# 111.net
KiCad netlist of a schematic drawn in Altium Designer
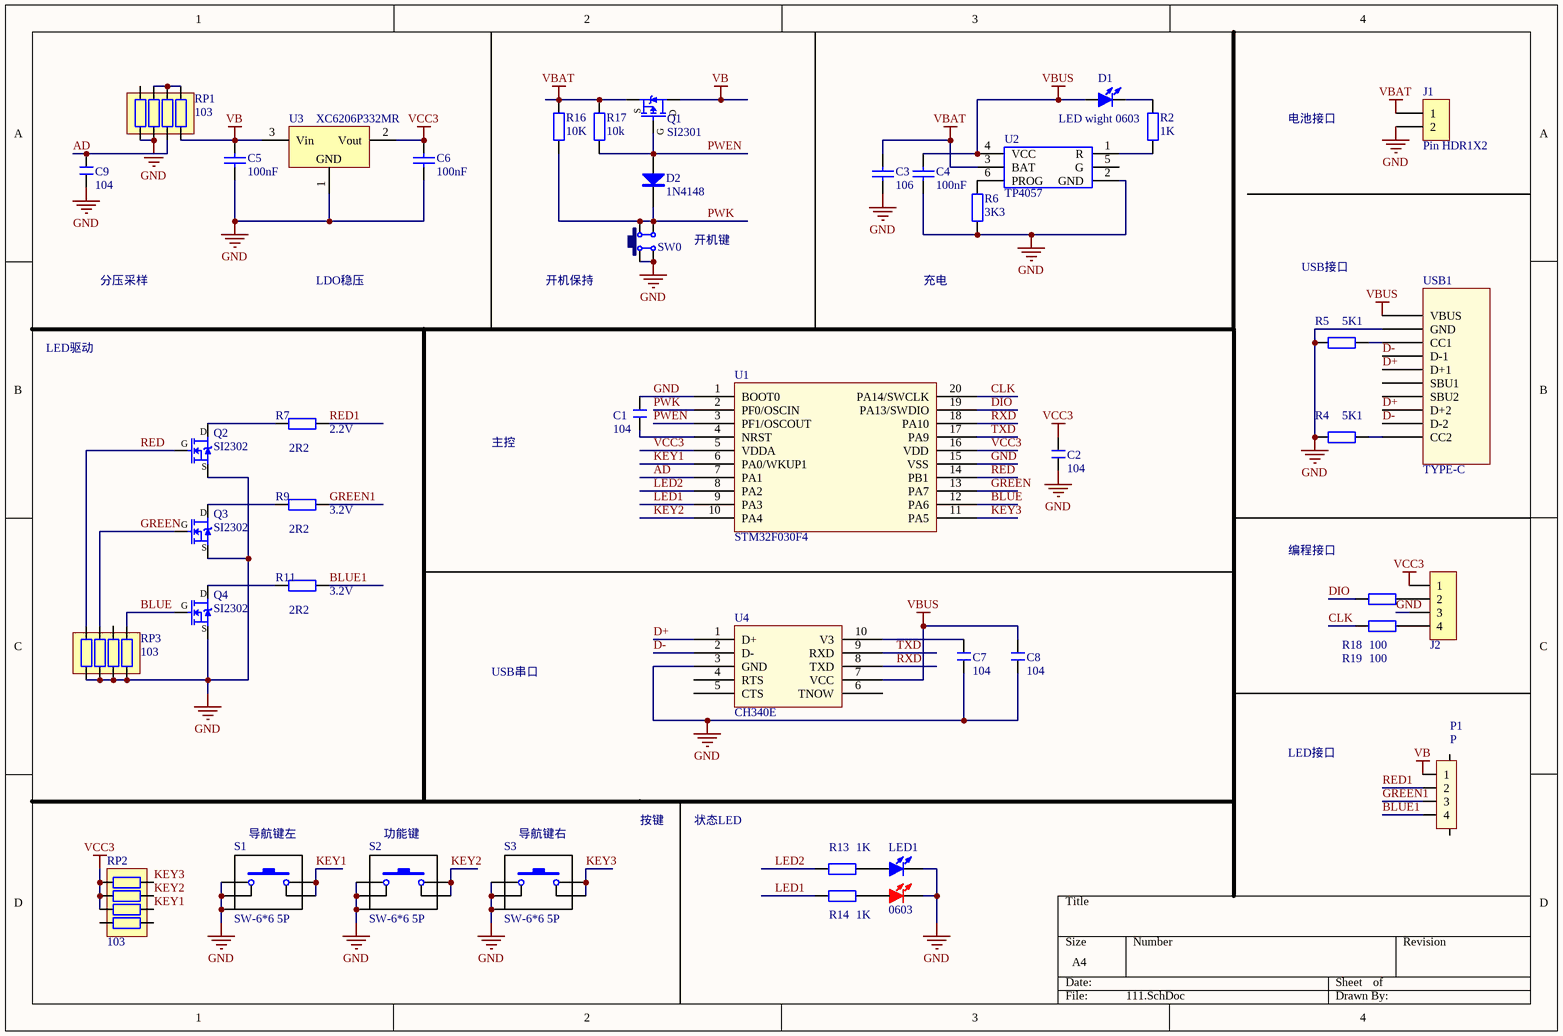
[diagram p0: 111.SchDoc]

(export (version "E")
  (design (tool "Eeschema 10.0.6"))
  (components
    (comp (ref "C1")
      (value "104")
      (footprint "C 0402_M")
      (description "无极性贴片电容")
      (libsource (lib "3.1   - 电阻-电容-电感") (part "C"))
    )
    (comp (ref "C2")
      (value "104")
      (footprint "C 0402_M")
      (description "无极性贴片电容")
      (libsource (lib "3.1   - 电阻-电容-电感") (part "C"))
    )
    (comp (ref "C3")
      (value "106")
      (footprint "C-RAD-0805")
      (description "无极性电容")
      (fields (field (name "Comment") "Cap") (field (name "PUBLISHER") "Altium Limited"))
      (libsource (lib "fszhang") (part "Cap"))
    )
    (comp (ref "C4")
      (value "100nF")
      (footprint "C-RAD-0603")
      (description "无极性电容")
      (fields (field (name "Comment") "Cap") (field (name "PUBLISHER") "Altium Limited"))
      (libsource (lib "fszhang") (part "Cap"))
    )
    (comp (ref "C5")
      (value "100nF")
      (footprint "C-RAD-0603")
      (description "无极性电容")
      (fields (field (name "Comment") "Cap") (field (name "PUBLISHER") "Altium Limited"))
      (libsource (lib "fszhang") (part "Cap"))
    )
    (comp (ref "C6")
      (value "100nF")
      (footprint "C-RAD-0603")
      (description "无极性电容")
      (fields (field (name "Comment") "Cap") (field (name "PUBLISHER") "Altium Limited"))
      (libsource (lib "fszhang") (part "Cap"))
    )
    (comp (ref "C7")
      (value "104")
      (footprint "C 0402_M")
      (description "无极性贴片电容")
      (libsource (lib "3.1   - 电阻-电容-电感") (part "C"))
    )
    (comp (ref "C8")
      (value "104")
      (footprint "C 0402_M")
      (description "无极性贴片电容")
      (libsource (lib "3.1   - 电阻-电容-电感") (part "C"))
    )
    (comp (ref "C9")
      (value "104")
      (footprint "C 0402_M")
      (description "无极性贴片电容")
      (libsource (lib "3.1   - 电阻-电容-电感") (part "C"))
    )
    (comp (ref "D1")
      (value "LED wight 0603")
      (footprint "LED 0603R")
      (description "贴片LED")
      (libsource (lib "9.1   - LED") (part "LED-SMD"))
    )
    (comp (ref "D2")
      (value "1N4148")
      (footprint "SOD-323")
      (description "高速开关二极管")
      (libsource (lib "8.1   - 二极管-整流桥") (part "1N4148"))
    )
    (comp (ref "J1") (value "Pin HDR1X2") (footprint "SH1.0_2pin") (libsource (lib "排针") (part "Pin HDR1X2")))
    (comp (ref "J2")
      (value "HDR-1X4")
      (footprint "HDR2.0-LI-4P")
      (description "4P接插件")
      (libsource (lib "4.5   - 接插件-脚距2.0") (part "Header 4"))
    )
    (comp (ref "LED1")
      (value "0603")
      (footprint "LED 0603-RG")
      (description "贴片双色LED")
      (libsource (lib "9.1   - LED") (part "LED-SMD-RG"))
    )
    (comp (ref "P1") (value "P") (footprint "SH1.0_4pin") (libsource (lib "0") (part "SH1.0-4")))
    (comp (ref "Q1")
      (value "SI2301")
      (footprint "SOT23-3N")
      (description "P沟道 20V/2.8A")
      (libsource (lib "6.1   - 场效应管-可控硅") (part "SI2301"))
    )
    (comp (ref "Q2")
      (value "SI2302")
      (footprint "SOT23-3N")
      (description "N沟道 20V/3A")
      (libsource (lib "6.1   - 场效应管-可控硅") (part "SI2302"))
    )
    (comp (ref "Q3")
      (value "SI2302")
      (footprint "SOT23-3N")
      (description "N沟道 20V/3A")
      (libsource (lib "6.1   - 场效应管-可控硅") (part "SI2302"))
    )
    (comp (ref "Q4")
      (value "SI2302")
      (footprint "SOT23-3N")
      (description "N沟道 20V/3A")
      (libsource (lib "6.1   - 场效应管-可控硅") (part "SI2302"))
    )
    (comp (ref "R2")
      (value "1K")
      (footprint "R 0402_M")
      (description "贴片电阻")
      (libsource (lib "3.1   - 电阻-电容-电感") (part "R"))
    )
    (comp (ref "R4")
      (value "5K1")
      (footprint "R 0402_M")
      (description "贴片电阻")
      (libsource (lib "3.1   - 电阻-电容-电感") (part "R"))
    )
    (comp (ref "R5")
      (value "5K1")
      (footprint "R 0402_M")
      (description "贴片电阻")
      (libsource (lib "3.1   - 电阻-电容-电感") (part "R"))
    )
    (comp (ref "R6")
      (value "3K3")
      (footprint "R 0402_M")
      (description "贴片电阻")
      (libsource (lib "3.1   - 电阻-电容-电感") (part "R"))
    )
    (comp (ref "R7")
      (value "2R2")
      (footprint "0603-1")
      (description "贴片电阻")
      (fields (field (name "PUBLISHER") "Altium Limited"))
      (libsource (lib "fszhang") (part "Res1"))
    )
    (comp (ref "R9")
      (value "2R2")
      (footprint "0603-1")
      (description "贴片电阻")
      (fields (field (name "PUBLISHER") "Altium Limited"))
      (libsource (lib "fszhang") (part "Res1"))
    )
    (comp (ref "R11")
      (value "2R2")
      (footprint "0603-1")
      (description "贴片电阻")
      (fields (field (name "PUBLISHER") "Altium Limited"))
      (libsource (lib "fszhang") (part "Res1"))
    )
    (comp (ref "R13")
      (value "1K")
      (footprint "R 0402_M")
      (description "贴片电阻")
      (libsource (lib "3.1   - 电阻-电容-电感") (part "R"))
    )
    (comp (ref "R14")
      (value "1K")
      (footprint "R 0402_M")
      (description "贴片电阻")
      (libsource (lib "3.1   - 电阻-电容-电感") (part "R"))
    )
    (comp (ref "R16")
      (value "10K")
      (footprint "R 0402_M")
      (description "贴片电阻")
      (libsource (lib "3.1   - 电阻-电容-电感") (part "R"))
    )
    (comp (ref "R17")
      (value "10k")
      (footprint "R 0402_M")
      (description "贴片电阻")
      (libsource (lib "3.1   - 电阻-电容-电感") (part "R"))
    )
    (comp (ref "R18")
      (value "100")
      (footprint "R 0402_M")
      (description "贴片电阻")
      (libsource (lib "3.1   - 电阻-电容-电感") (part "R"))
    )
    (comp (ref "R19")
      (value "100")
      (footprint "R 0402_M")
      (description "贴片电阻")
      (libsource (lib "3.1   - 电阻-电容-电感") (part "R"))
    )
    (comp (ref "RP1")
      (value "103")
      (footprint "RCA-8P4R-0402")
      (description "贴片网络排阻")
      (libsource (lib "3.1   - 电阻-电容-电感") (part "R-8P4R"))
    )
    (comp (ref "RP2")
      (value "103")
      (footprint "RCA-8P4R-0402")
      (description "贴片网络排阻")
      (libsource (lib "") (part "R-8P4R_1"))
    )
    (comp (ref "RP3")
      (value "103")
      (footprint "RCA-8P4R-0402")
      (description "贴片网络排阻")
      (libsource (lib "3.1   - 电阻-电容-电感") (part "R-8P4R"))
    )
    (comp (ref "S1")
      (value "SW-6*6 5P")
      (footprint "BUTTON-5Pin")
      (description "微动开关")
      (fields (field (name "PUBLISHER") "Altium Limited"))
      (libsource (lib "fszhang") (part "SW-6*6 5P"))
    )
    (comp (ref "S2")
      (value "SW-6*6 5P")
      (footprint "BUTTON-5Pin")
      (description "微动开关")
      (fields (field (name "PUBLISHER") "Altium Limited"))
      (libsource (lib "fszhang") (part "SW-6*6 5P"))
    )
    (comp (ref "S3")
      (value "SW-6*6 5P")
      (footprint "BUTTON-5Pin")
      (description "微动开关")
      (fields (field (name "PUBLISHER") "Altium Limited"))
      (libsource (lib "fszhang") (part "SW-6*6 5P"))
    )
    (comp (ref "SW0")
      (value "4x4x0.8")
      (footprint "TS-027A")
      (description "薄膜轻触开关")
      (libsource (lib "5.1   - 按键-开关") (part "TS-027A"))
    )
    (comp (ref "U1")
      (value "STM32F030F4")
      (footprint "TSSOP20")
      (libsource (lib "fszhang") (part "STM32F030F4"))
    )
    (comp (ref "U2") (value "TP4057") (footprint "SOT23-6") (libsource (lib "常用") (part "TP4057")))
    (comp (ref "U3")
      (value "XC6206P332MR")
      (footprint "SOT23-3N")
      (description "低压差线性稳压芯片")
      (libsource (lib "1.3   - 电源类芯片") (part "XC6206P332MR"))
    )
    (comp (ref "U4") (value "CH340E") (footprint "MSOP10_M") (libsource (lib "1") (part "CH340E")))
    (comp (ref "USB1") (value "TYPE-C") (footprint "TYPE-C") (libsource (lib "1") (part "USB-C")))
  )
  (nets
    (net (code "1") (name "/AD") (class "Default")
      (node (ref "C9") (pin "2") (pinfunction "2_2") (pintype "passive"))
      (node (ref "RP1") (pin "3") (pinfunction "3_3") (pintype "passive"))
      (node (ref "U1") (pin "7") (pinfunction "PA1_7") (pintype "passive"))
    )
    (net (code "2") (name "/BLUE") (class "Default")
      (node (ref "Q4") (pin "1") (pinfunction "G_1") (pintype "passive"))
      (node (ref "RP3") (pin "5") (pinfunction "5_5") (pintype "passive"))
      (node (ref "U1") (pin "12") (pinfunction "PA6_12") (pintype "passive"))
    )
    (net (code "3") (name "/BLUE1") (class "Default")
      (node (ref "P1") (pin "4") (pinfunction "4_4") (pintype "passive"))
      (node (ref "R11") (pin "2") (pinfunction "2_2") (pintype "passive"))
    )
    (net (code "4") (name "/CLK") (class "Default")
      (node (ref "R19") (pin "2") (pinfunction "2_2") (pintype "passive"))
      (node (ref "U1") (pin "20") (pinfunction "PA14/SWCLK_20") (pintype "passive"))
    )
    (net (code "5") (name "/D+") (class "Default")
      (node (ref "U4") (pin "1") (pinfunction "D+_1") (pintype "passive"))
      (node (ref "USB1") (pin "D+1") (pinfunction "D+1_D+1") (pintype "passive"))
      (node (ref "USB1") (pin "D+2") (pinfunction "D+2_D+2") (pintype "passive"))
    )
    (net (code "6") (name "/D-") (class "Default")
      (node (ref "U4") (pin "2") (pinfunction "D-_2") (pintype "passive"))
      (node (ref "USB1") (pin "D-1") (pinfunction "D-1_D-1") (pintype "passive"))
      (node (ref "USB1") (pin "D-2") (pinfunction "D-2_D-2") (pintype "passive"))
    )
    (net (code "7") (name "/DIO") (class "Default")
      (node (ref "R18") (pin "2") (pinfunction "2_2") (pintype "passive"))
      (node (ref "U1") (pin "19") (pinfunction "PA13/SWDIO_19") (pintype "passive"))
    )
    (net (code "8") (name "/GREEN") (class "Default")
      (node (ref "Q3") (pin "1") (pinfunction "G_1") (pintype "passive"))
      (node (ref "RP3") (pin "7") (pinfunction "7_7") (pintype "passive"))
      (node (ref "U1") (pin "13") (pinfunction "PA7_13") (pintype "passive"))
    )
    (net (code "9") (name "/GREEN1") (class "Default")
      (node (ref "P1") (pin "3") (pinfunction "3_3") (pintype "passive"))
      (node (ref "R9") (pin "2") (pinfunction "2_2") (pintype "passive"))
    )
    (net (code "10") (name "/KEY1") (class "Default")
      (node (ref "RP2") (pin "2") (pinfunction "2_2") (pintype "passive"))
      (node (ref "S1") (pin "2") (pinfunction "2_2") (pintype "passive"))
      (node (ref "S1") (pin "3") (pinfunction "3_3") (pintype "passive"))
      (node (ref "U1") (pin "6") (pinfunction "PA0/WKUP1_6") (pintype "passive"))
    )
    (net (code "11") (name "/KEY2") (class "Default")
      (node (ref "RP2") (pin "3") (pinfunction "3_3") (pintype "passive"))
      (node (ref "S2") (pin "2") (pinfunction "2_2") (pintype "passive"))
      (node (ref "S2") (pin "3") (pinfunction "3_3") (pintype "passive"))
      (node (ref "U1") (pin "10") (pinfunction "PA4_10") (pintype "passive"))
    )
    (net (code "12") (name "/KEY3") (class "Default")
      (node (ref "RP2") (pin "4") (pinfunction "4_4") (pintype "passive"))
      (node (ref "S3") (pin "2") (pinfunction "2_2") (pintype "passive"))
      (node (ref "S3") (pin "3") (pinfunction "3_3") (pintype "passive"))
      (node (ref "U1") (pin "11") (pinfunction "PA5_11") (pintype "passive"))
    )
    (net (code "13") (name "/LED1") (class "Default")
      (node (ref "R14") (pin "1") (pinfunction "1_1") (pintype "passive"))
      (node (ref "U1") (pin "9") (pinfunction "PA3_9") (pintype "passive"))
    )
    (net (code "14") (name "/LED2") (class "Default")
      (node (ref "R13") (pin "1") (pinfunction "1_1") (pintype "passive"))
      (node (ref "U1") (pin "8") (pinfunction "PA2_8") (pintype "passive"))
    )
    (net (code "15") (name "/PWEN") (class "Default")
      (node (ref "D2") (pin "A") (pinfunction "A_A") (pintype "passive"))
      (node (ref "Q1") (pin "1") (pinfunction "G_1") (pintype "passive"))
      (node (ref "R17") (pin "1") (pinfunction "1_1") (pintype "passive"))
      (node (ref "U1") (pin "3") (pinfunction "PF1/OSCOUT_3") (pintype "passive"))
    )
    (net (code "16") (name "/PWK") (class "Default")
      (node (ref "D2") (pin "K") (pinfunction "K_K") (pintype "passive"))
      (node (ref "R16") (pin "1") (pinfunction "1_1") (pintype "passive"))
      (node (ref "SW0") (pin "2") (pinfunction "2_2") (pintype "passive"))
      (node (ref "SW0") (pin "3") (pinfunction "3_3") (pintype "passive"))
      (node (ref "U1") (pin "2") (pinfunction "PF0/OSCIN_2") (pintype "passive"))
    )
    (net (code "17") (name "/RED") (class "Default")
      (node (ref "Q2") (pin "1") (pinfunction "G_1") (pintype "passive"))
      (node (ref "RP3") (pin "8") (pinfunction "8_8") (pintype "passive"))
      (node (ref "U1") (pin "14") (pinfunction "PB1_14") (pintype "passive"))
    )
    (net (code "18") (name "/RED1") (class "Default")
      (node (ref "P1") (pin "2") (pinfunction "2_2") (pintype "passive"))
      (node (ref "R7") (pin "2") (pinfunction "2_2") (pintype "passive"))
    )
    (net (code "19") (name "/RXD") (class "Default")
      (node (ref "U1") (pin "18") (pinfunction "PA10_18") (pintype "passive"))
      (node (ref "U4") (pin "8") (pinfunction "TXD_8") (pintype "passive"))
    )
    (net (code "20") (name "/TXD") (class "Default")
      (node (ref "U1") (pin "17") (pinfunction "PA9_17") (pintype "passive"))
      (node (ref "U4") (pin "9") (pinfunction "RXD_9") (pintype "passive"))
    )
    (net (code "21") (name "GND") (class "Default")
      (node (ref "C1") (pin "2") (pinfunction "2_2") (pintype "passive"))
      (node (ref "C2") (pin "2") (pinfunction "2_2") (pintype "passive"))
      (node (ref "C3") (pin "1") (pinfunction "1_1") (pintype "passive"))
      (node (ref "C4") (pin "1") (pinfunction "1_1") (pintype "passive"))
      (node (ref "C5") (pin "1") (pinfunction "1_1") (pintype "passive"))
      (node (ref "C6") (pin "1") (pinfunction "1_1") (pintype "passive"))
      (node (ref "C7") (pin "1") (pinfunction "1_1") (pintype "passive"))
      (node (ref "C8") (pin "1") (pinfunction "1_1") (pintype "passive"))
      (node (ref "C9") (pin "1") (pinfunction "1_1") (pintype "passive"))
      (node (ref "J1") (pin "2") (pinfunction "2_2") (pintype "passive"))
      (node (ref "J2") (pin "3") (pinfunction "3_3") (pintype "passive"))
      (node (ref "LED1") (pin "3") (pinfunction "3_3") (pintype "passive"))
      (node (ref "LED1") (pin "4") (pinfunction "4_4") (pintype "passive"))
      (node (ref "Q2") (pin "2") (pinfunction "S_2") (pintype "passive"))
      (node (ref "Q3") (pin "2") (pinfunction "S_2") (pintype "passive"))
      (node (ref "Q4") (pin "2") (pinfunction "S_2") (pintype "passive"))
      (node (ref "R4") (pin "2") (pinfunction "2_2") (pintype "passive"))
      (node (ref "R5") (pin "2") (pinfunction "2_2") (pintype "passive"))
      (node (ref "R6") (pin "1") (pinfunction "1_1") (pintype "passive"))
      (node (ref "RP1") (pin "1") (pinfunction "1_1") (pintype "passive"))
      (node (ref "RP1") (pin "2") (pinfunction "2_2") (pintype "passive"))
      (node (ref "RP3") (pin "1") (pinfunction "1_1") (pintype "passive"))
      (node (ref "RP3") (pin "2") (pinfunction "2_2") (pintype "passive"))
      (node (ref "RP3") (pin "3") (pinfunction "3_3") (pintype "passive"))
      (node (ref "RP3") (pin "4") (pinfunction "4_4") (pintype "passive"))
      (node (ref "S1") (pin "1") (pinfunction "1_1") (pintype "passive"))
      (node (ref "S1") (pin "4") (pinfunction "4_4") (pintype "passive"))
      (node (ref "S1") (pin "5") (pinfunction "5_5") (pintype "passive"))
      (node (ref "S2") (pin "1") (pinfunction "1_1") (pintype "passive"))
      (node (ref "S2") (pin "4") (pinfunction "4_4") (pintype "passive"))
      (node (ref "S2") (pin "5") (pinfunction "5_5") (pintype "passive"))
      (node (ref "S3") (pin "1") (pinfunction "1_1") (pintype "passive"))
      (node (ref "S3") (pin "4") (pinfunction "4_4") (pintype "passive"))
      (node (ref "S3") (pin "5") (pinfunction "5_5") (pintype "passive"))
      (node (ref "SW0") (pin "1") (pinfunction "1_1") (pintype "passive"))
      (node (ref "SW0") (pin "4") (pinfunction "4_4") (pintype "passive"))
      (node (ref "U1") (pin "1") (pinfunction "BOOT0_1") (pintype "passive"))
      (node (ref "U1") (pin "15") (pinfunction "VSS_15") (pintype "passive"))
      (node (ref "U2") (pin "2") (pinfunction "GND_2") (pintype "passive"))
      (node (ref "U3") (pin "1") (pinfunction "GND_1") (pintype "passive"))
      (node (ref "U4") (pin "3") (pinfunction "GND_3") (pintype "passive"))
      (node (ref "USB1") (pin "GND") (pinfunction "GND_GND") (pintype "passive"))
    )
    (net (code "22") (name "Net-(D1-K)") (class "Default")
      (node (ref "D1") (pin "2") (pinfunction "K_2") (pintype "passive"))
      (node (ref "R2") (pin "2") (pinfunction "2_2") (pintype "passive"))
    )
    (net (code "23") (name "Net-(J2-Pad2)") (class "Default")
      (node (ref "J2") (pin "2") (pinfunction "2_2") (pintype "passive"))
      (node (ref "R18") (pin "1") (pinfunction "1_1") (pintype "passive"))
    )
    (net (code "24") (name "Net-(J2-Pad4)") (class "Default")
      (node (ref "J2") (pin "4") (pinfunction "4_4") (pintype "passive"))
      (node (ref "R19") (pin "1") (pinfunction "1_1") (pintype "passive"))
    )
    (net (code "25") (name "Net-(LED1-1-Pad2)") (class "Default")
      (node (ref "LED1") (pin "2") (pinfunction "1_2") (pintype "passive"))
      (node (ref "R14") (pin "2") (pinfunction "2_2") (pintype "passive"))
    )
    (net (code "26") (name "Net-(LED1-Pad1)") (class "Default")
      (node (ref "LED1") (pin "1") (pinfunction "1_1") (pintype "passive"))
      (node (ref "R13") (pin "2") (pinfunction "2_2") (pintype "passive"))
    )
    (net (code "27") (name "Net-(Q2-D)") (class "Default")
      (node (ref "Q2") (pin "3") (pinfunction "D_3") (pintype "passive"))
      (node (ref "R7") (pin "1") (pinfunction "1_1") (pintype "passive"))
    )
    (net (code "28") (name "Net-(Q3-D)") (class "Default")
      (node (ref "Q3") (pin "3") (pinfunction "D_3") (pintype "passive"))
      (node (ref "R9") (pin "1") (pinfunction "1_1") (pintype "passive"))
    )
    (net (code "29") (name "Net-(Q4-D)") (class "Default")
      (node (ref "Q4") (pin "3") (pinfunction "D_3") (pintype "passive"))
      (node (ref "R11") (pin "1") (pinfunction "1_1") (pintype "passive"))
    )
    (net (code "30") (name "Net-(R4-Pad1)") (class "Default")
      (node (ref "R4") (pin "1") (pinfunction "1_1") (pintype "passive"))
      (node (ref "USB1") (pin "CC2") (pinfunction "CC2_CC2") (pintype "passive"))
    )
    (net (code "31") (name "Net-(R5-Pad1)") (class "Default")
      (node (ref "R5") (pin "1") (pinfunction "1_1") (pintype "passive"))
      (node (ref "USB1") (pin "CC1") (pinfunction "CC1_CC1") (pintype "passive"))
    )
    (net (code "32") (name "Net-(RP1-Pad5)") (class "Default")
      (node (ref "RP1") (pin "5") (pinfunction "5_5") (pintype "passive"))
      (node (ref "RP1") (pin "6") (pinfunction "6_6") (pintype "passive"))
      (node (ref "RP1") (pin "7") (pinfunction "7_7") (pintype "passive"))
    )
    (net (code "33") (name "Net-(U1-NRST)") (class "Default")
      (node (ref "C1") (pin "1") (pinfunction "1_1") (pintype "passive"))
      (node (ref "U1") (pin "4") (pinfunction "NRST_4") (pintype "passive"))
    )
    (net (code "34") (name "Net-(U2-PROG)") (class "Default")
      (node (ref "R6") (pin "2") (pinfunction "2_2") (pintype "passive"))
      (node (ref "U2") (pin "6") (pinfunction "PROG_6") (pintype "passive"))
    )
    (net (code "35") (name "Net-(U2-R)") (class "Default")
      (node (ref "R2") (pin "1") (pinfunction "1_1") (pintype "passive"))
      (node (ref "U2") (pin "1") (pinfunction "R_1") (pintype "passive"))
    )
    (net (code "36") (name "Net-(U4-V3)") (class "Default")
      (node (ref "C7") (pin "2") (pinfunction "2_2") (pintype "passive"))
      (node (ref "U4") (pin "10") (pinfunction "V3_10") (pintype "passive"))
    )
    (net (code "37") (name "VB") (class "Default")
      (node (ref "C5") (pin "2") (pinfunction "2_2") (pintype "passive"))
      (node (ref "P1") (pin "1") (pinfunction "1_1") (pintype "passive"))
      (node (ref "Q1") (pin "3") (pinfunction "D_3") (pintype "passive"))
      (node (ref "RP1") (pin "4") (pinfunction "4_4") (pintype "passive"))
      (node (ref "U3") (pin "3") (pinfunction "Vin_3") (pintype "passive"))
    )
    (net (code "38") (name "VBAT") (class "Default")
      (node (ref "C3") (pin "2") (pinfunction "2_2") (pintype "passive"))
      (node (ref "J1") (pin "1") (pinfunction "1_1") (pintype "passive"))
      (node (ref "Q1") (pin "2") (pinfunction "S_2") (pintype "passive"))
      (node (ref "R16") (pin "2") (pinfunction "2_2") (pintype "passive"))
      (node (ref "R17") (pin "2") (pinfunction "2_2") (pintype "passive"))
      (node (ref "U2") (pin "3") (pinfunction "BAT_3") (pintype "passive"))
    )
    (net (code "39") (name "VBUS") (class "Default")
      (node (ref "C4") (pin "2") (pinfunction "2_2") (pintype "passive"))
      (node (ref "C8") (pin "2") (pinfunction "2_2") (pintype "passive"))
      (node (ref "D1") (pin "1") (pinfunction "A_1") (pintype "passive"))
      (node (ref "U2") (pin "4") (pinfunction "VCC_4") (pintype "passive"))
      (node (ref "U4") (pin "7") (pinfunction "VCC_7") (pintype "passive"))
      (node (ref "USB1") (pin "VBUS") (pinfunction "VBUS_VBUS") (pintype "passive"))
    )
    (net (code "40") (name "VCC3") (class "Default")
      (node (ref "C2") (pin "1") (pinfunction "1_1") (pintype "passive"))
      (node (ref "C6") (pin "2") (pinfunction "2_2") (pintype "passive"))
      (node (ref "J2") (pin "1") (pinfunction "1_1") (pintype "passive"))
      (node (ref "RP2") (pin "5") (pinfunction "5_5") (pintype "passive"))
      (node (ref "RP2") (pin "6") (pinfunction "6_6") (pintype "passive"))
      (node (ref "RP2") (pin "7") (pinfunction "7_7") (pintype "passive"))
      (node (ref "U1") (pin "16") (pinfunction "VDD_16") (pintype "passive"))
      (node (ref "U1") (pin "5") (pinfunction "VDDA_5") (pintype "passive"))
      (node (ref "U3") (pin "2") (pinfunction "Vout_2") (pintype "passive"))
    )
    (net (code "41") (name "unconnected-(P1-Pad0)") (class "Default")
      (node (ref "P1") (pin "0") (pinfunction "0_0") (pintype "passive"))
    )
    (net (code "42") (name "unconnected-(P1-Pad0)_1") (class "Default")
      (node (ref "P1") (pin "0") (pinfunction "0_0") (pintype "passive"))
    )
    (net (code "43") (name "unconnected-(RP1-Pad8)") (class "Default")
      (node (ref "RP1") (pin "8") (pinfunction "8_8") (pintype "passive"))
    )
    (net (code "44") (name "unconnected-(RP2-Pad1)") (class "Default")
      (node (ref "RP2") (pin "1") (pinfunction "1_1") (pintype "passive"))
    )
    (net (code "45") (name "unconnected-(RP2-Pad8)") (class "Default")
      (node (ref "RP2") (pin "8") (pinfunction "8_8") (pintype "passive"))
    )
    (net (code "46") (name "unconnected-(RP3-Pad6)") (class "Default")
      (node (ref "RP3") (pin "6") (pinfunction "6_6") (pintype "passive"))
    )
    (net (code "47") (name "unconnected-(U2-G-Pad5)") (class "Default")
      (node (ref "U2") (pin "5") (pinfunction "G_5") (pintype "passive"))
    )
    (net (code "48") (name "unconnected-(U4-CTS-Pad5)") (class "Default")
      (node (ref "U4") (pin "5") (pinfunction "CTS_5") (pintype "passive"))
    )
    (net (code "49") (name "unconnected-(U4-RTS-Pad4)") (class "Default")
      (node (ref "U4") (pin "4") (pinfunction "RTS_4") (pintype "passive"))
    )
    (net (code "50") (name "unconnected-(U4-TNOW-Pad6)") (class "Default")
      (node (ref "U4") (pin "6") (pinfunction "TNOW_6") (pintype "passive"))
    )
    (net (code "51") (name "unconnected-(USB1-PadSBU1)") (class "Default")
      (node (ref "USB1") (pin "SBU1") (pinfunction "SBU1_SBU1") (pintype "passive"))
    )
    (net (code "52") (name "unconnected-(USB1-PadSBU2)") (class "Default")
      (node (ref "USB1") (pin "SBU2") (pinfunction "SBU2_SBU2") (pintype "passive"))
    )
  )
)
